# WIFI.net
KiCad netlist of a schematic drawn in Altium Designer
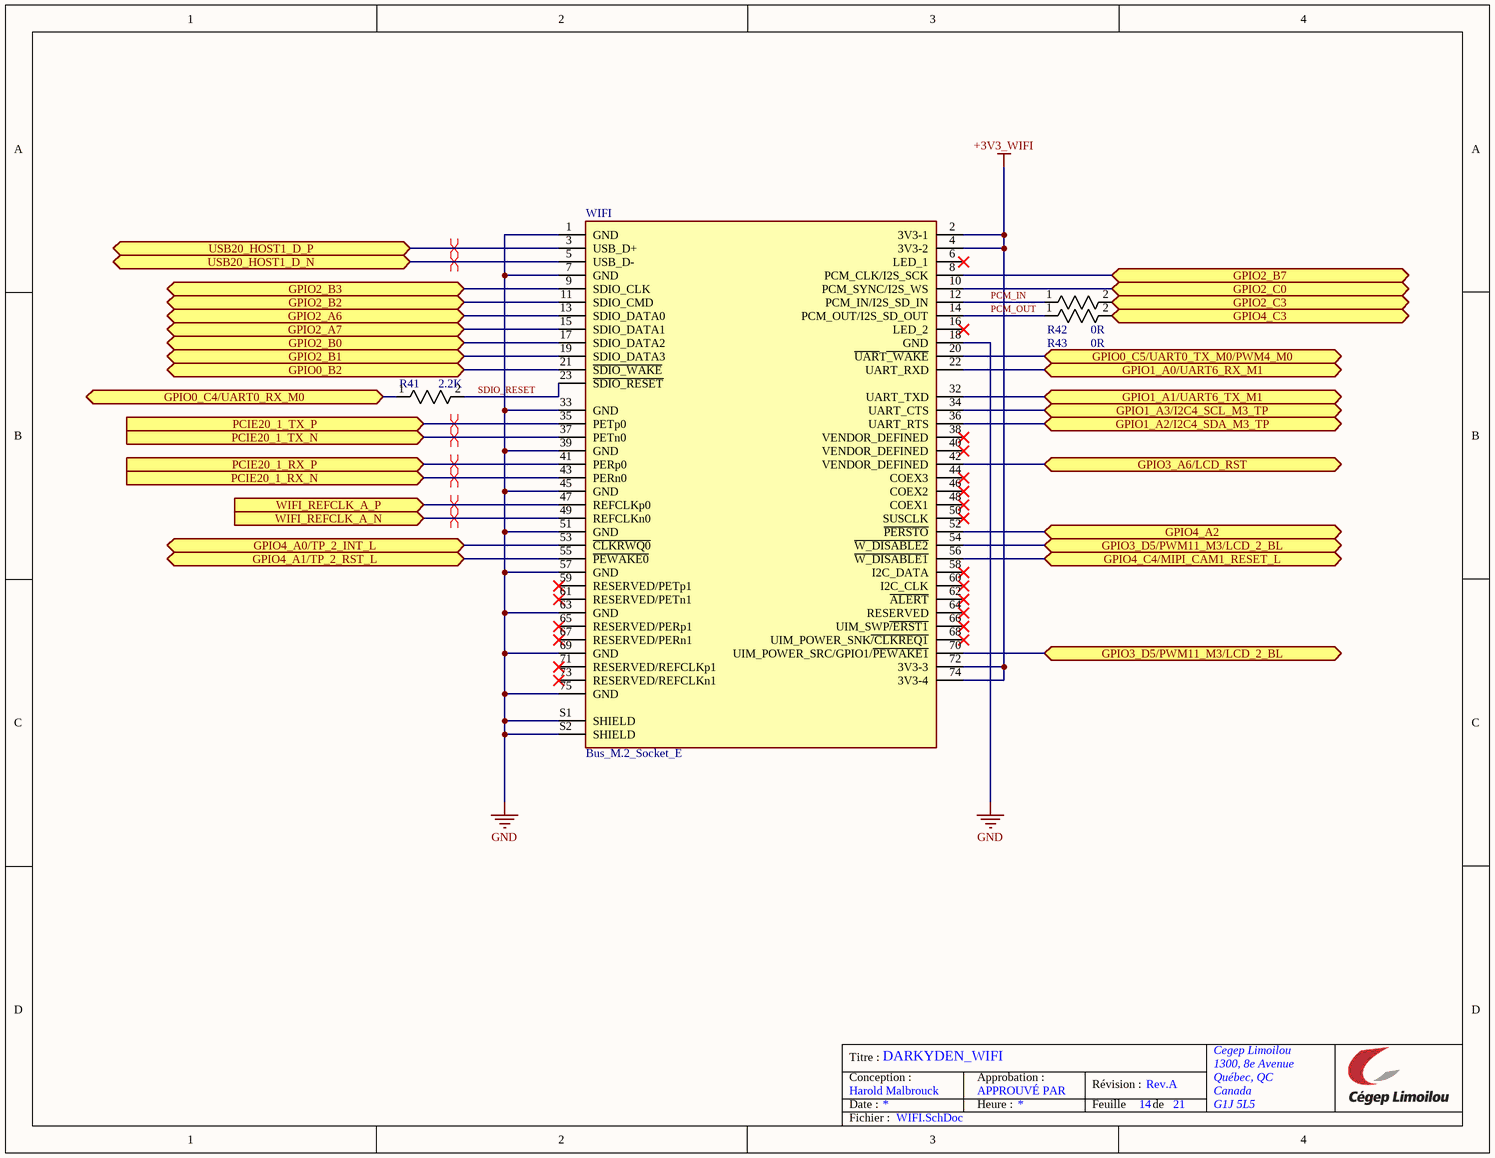
[diagram p0: WIFI.SchDoc]

(export (version "E")
  (design (tool "Eeschema 10.0.6"))
  (components
    (comp (ref "R41")
      (value "2.2K")
      (footprint "SamacSys:RESC1608X55N")
      (description "2.2 kOhm, ï¿½ 5%, 100 mW, 0603 [1608 Metric], Thick Film, General Purpose")
      (fields
        (field (name "MOUSER PART NUMBER") "667-ERJ-3GEYJ222V")
        (field (name "ARROW PART NUMBER") "ERJ-3GEYJ222V")
      )
      (libsource (lib "DARKYDEN") (part "ERJ-3GEYJ222V"))
    )
    (comp (ref "R42")
      (value "0R")
      (footprint "SamacSys:RESC1608X55N")
      (description "Zero Ohm Resistor, Jumper, 0603 [1608 Metric], Thick Film, 100 mW, 1 A, Surface Mount")
      (fields
        (field (name "MOUSER PART NUMBER") "667-ERJ-3GEY0R00V")
        (field (name "ARROW PART NUMBER") "ERJ-3GEY0R00V")
      )
      (libsource (lib "DARKYDEN") (part "ERJ-3GEY0R00V"))
    )
    (comp (ref "R43")
      (value "0R")
      (footprint "SamacSys:RESC1608X55N")
      (description "Zero Ohm Resistor, Jumper, 0603 [1608 Metric], Thick Film, 100 mW, 1 A, Surface Mount")
      (fields
        (field (name "MOUSER PART NUMBER") "667-ERJ-3GEY0R00V")
        (field (name "ARROW PART NUMBER") "ERJ-3GEY0R00V")
      )
      (libsource (lib "DARKYDEN") (part "ERJ-3GEY0R00V"))
    )
    (comp (ref "WIFI")
      (value "Bus_M.2_Socket_E")
      (footprint "AMPHENOL_MDT320E01001")
      (description "PCIe M.2 Connectors, Storage and Server Connector, P=0.5mm, H=3.2mm, Key E,30Î¼in Au Plating")
      (fields (field (name "MANUFACTURER PART NUMBER") "MDT320E01001") (field (name "MF") "Amphenol ICC"))
      (libsource (lib "Bus_M.2_Socket_E") (part "Bus_M.2_Socket_E"))
    )
  )
  (nets
    (net (code "1") (name "+3V3_WIFI") (class "Default")
      (node (ref "WIFI") (pin "2") (pinfunction "3V3-1_2") (pintype "power_in"))
      (node (ref "WIFI") (pin "4") (pinfunction "3V3-2_4") (pintype "power_in"))
      (node (ref "WIFI") (pin "72") (pinfunction "3V3-3_72") (pintype "power_in"))
      (node (ref "WIFI") (pin "74") (pinfunction "3V3-4_74") (pintype "power_in"))
    )
    (net (code "2") (name "/GPIO0_B2") (class "Default")
      (node (ref "WIFI") (pin "21") (pinfunction "~{SDIO_WAKE}_21") (pintype "passive"))
    )
    (net (code "3") (name "/GPIO0_C4{slash}UART0_RX_M0") (class "Default")
      (node (ref "R41") (pin "1") (pinfunction "1_1") (pintype "passive"))
    )
    (net (code "4") (name "/GPIO0_C5{slash}UART0_TX_M0{slash}PWM4_M0") (class "Default")
      (node (ref "WIFI") (pin "20") (pinfunction "~{UAR}T~{_WAKE}_20") (pintype "passive"))
    )
    (net (code "5") (name "/GPIO1_A0{slash}UART6_RX_M1") (class "Default")
      (node (ref "WIFI") (pin "22") (pinfunction "UART_RXD_22") (pintype "passive"))
    )
    (net (code "6") (name "/GPIO1_A1{slash}UART6_TX_M1") (class "Default")
      (node (ref "WIFI") (pin "32") (pinfunction "UART_TXD_32") (pintype "passive"))
    )
    (net (code "7") (name "/GPIO1_A2{slash}I2C4_SDA_M3_TP") (class "Default")
      (node (ref "WIFI") (pin "36") (pinfunction "UART_RTS_36") (pintype "passive"))
    )
    (net (code "8") (name "/GPIO1_A3{slash}I2C4_SCL_M3_TP") (class "Default")
      (node (ref "WIFI") (pin "34") (pinfunction "UART_CTS_34") (pintype "passive"))
    )
    (net (code "9") (name "/GPIO2_A6") (class "Default")
      (node (ref "WIFI") (pin "13") (pinfunction "SDIO_DATA0_13") (pintype "passive"))
    )
    (net (code "10") (name "/GPIO2_A7") (class "Default")
      (node (ref "WIFI") (pin "15") (pinfunction "SDIO_DATA1_15") (pintype "passive"))
    )
    (net (code "11") (name "/GPIO2_B0") (class "Default")
      (node (ref "WIFI") (pin "17") (pinfunction "SDIO_DATA2_17") (pintype "passive"))
    )
    (net (code "12") (name "/GPIO2_B1") (class "Default")
      (node (ref "WIFI") (pin "19") (pinfunction "SDIO_DATA3_19") (pintype "passive"))
    )
    (net (code "13") (name "/GPIO2_B2") (class "Default")
      (node (ref "WIFI") (pin "11") (pinfunction "SDIO_CMD_11") (pintype "passive"))
    )
    (net (code "14") (name "/GPIO2_B3") (class "Default")
      (node (ref "WIFI") (pin "9") (pinfunction "SDIO_CLK_9") (pintype "passive"))
    )
    (net (code "15") (name "/GPIO2_B7") (class "Default")
      (node (ref "WIFI") (pin "8") (pinfunction "PCM_CLK/I2S_SCK_8") (pintype "passive"))
    )
    (net (code "16") (name "/GPIO2_C0") (class "Default")
      (node (ref "WIFI") (pin "10") (pinfunction "PCM_SYNC/I2S_WS_10") (pintype "passive"))
    )
    (net (code "17") (name "/GPIO2_C3") (class "Default")
      (node (ref "R42") (pin "2") (pinfunction "2_2") (pintype "passive"))
    )
    (net (code "18") (name "/GPIO3_A6{slash}LCD_RST") (class "Default")
      (node (ref "WIFI") (pin "42") (pinfunction "VENDOR_DEFINED_42") (pintype "passive"))
    )
    (net (code "19") (name "/GPIO3_D5{slash}PWM11_M3{slash}LCD_2_BL") (class "Default")
      (node (ref "WIFI") (pin "54") (pinfunction "~{W_DISABLE2}_54") (pintype "passive"))
      (node (ref "WIFI") (pin "70") (pinfunction "UIM_POWER_SRC/GPIO1/~{PEWAKE1}_70") (pintype "passive"))
    )
    (net (code "20") (name "/GPIO4_A0{slash}TP_2_INT_L") (class "Default")
      (node (ref "WIFI") (pin "53") (pinfunction "~{CLKRWQ0}_53") (pintype "passive"))
    )
    (net (code "21") (name "/GPIO4_A1{slash}TP_2_RST_L") (class "Default")
      (node (ref "WIFI") (pin "55") (pinfunction "~{PEWAKE0}_55") (pintype "passive"))
    )
    (net (code "22") (name "/GPIO4_A2") (class "Default")
      (node (ref "WIFI") (pin "52") (pinfunction "~{PERSTO}_52") (pintype "passive"))
    )
    (net (code "23") (name "/GPIO4_C3") (class "Default")
      (node (ref "R43") (pin "2") (pinfunction "2_2") (pintype "passive"))
    )
    (net (code "24") (name "/GPIO4_C4{slash}MIPI_CAM1_RESET_L") (class "Default")
      (node (ref "WIFI") (pin "56") (pinfunction "~{W_DISABLE1}_56") (pintype "passive"))
    )
    (net (code "25") (name "/PCIE20_1_RX_N") (class "Default")
      (node (ref "WIFI") (pin "43") (pinfunction "PERn0_43") (pintype "passive"))
    )
    (net (code "26") (name "/PCIE20_1_RX_P") (class "Default")
      (node (ref "WIFI") (pin "41") (pinfunction "PERp0_41") (pintype "passive"))
    )
    (net (code "27") (name "/PCIE20_1_TX_N") (class "Default")
      (node (ref "WIFI") (pin "37") (pinfunction "PETn0_37") (pintype "passive"))
    )
    (net (code "28") (name "/PCIE20_1_TX_P") (class "Default")
      (node (ref "WIFI") (pin "35") (pinfunction "PETp0_35") (pintype "passive"))
    )
    (net (code "29") (name "/PCM_IN") (class "Default")
      (node (ref "R42") (pin "1") (pinfunction "1_1") (pintype "passive"))
      (node (ref "WIFI") (pin "12") (pinfunction "PCM_IN/I2S_SD_IN_12") (pintype "passive"))
    )
    (net (code "30") (name "/PCM_OUT") (class "Default")
      (node (ref "R43") (pin "1") (pinfunction "1_1") (pintype "passive"))
      (node (ref "WIFI") (pin "14") (pinfunction "PCM_OUT/I2S_SD_OUT_14") (pintype "passive"))
    )
    (net (code "31") (name "/SDIO_RESET") (class "Default")
      (node (ref "R41") (pin "2") (pinfunction "2_2") (pintype "passive"))
      (node (ref "WIFI") (pin "23") (pinfunction "~{SDIO_RESET}_23") (pintype "passive"))
    )
    (net (code "32") (name "/USB20_HOST1_D_N") (class "Default")
      (node (ref "WIFI") (pin "5") (pinfunction "USB_D-_5") (pintype "passive"))
    )
    (net (code "33") (name "/USB20_HOST1_D_P") (class "Default")
      (node (ref "WIFI") (pin "3") (pinfunction "USB_D+_3") (pintype "passive"))
    )
    (net (code "34") (name "/WIFI_REFCLK_A_N") (class "Default")
      (node (ref "WIFI") (pin "49") (pinfunction "REFCLKn0_49") (pintype "passive"))
    )
    (net (code "35") (name "/WIFI_REFCLK_A_P") (class "Default")
      (node (ref "WIFI") (pin "47") (pinfunction "REFCLKp0_47") (pintype "passive"))
    )
    (net (code "36") (name "GND") (class "Default")
      (node (ref "WIFI") (pin "1") (pinfunction "GND_1") (pintype "passive"))
      (node (ref "WIFI") (pin "18") (pinfunction "GND_18") (pintype "passive"))
      (node (ref "WIFI") (pin "33") (pinfunction "GND_33") (pintype "passive"))
      (node (ref "WIFI") (pin "39") (pinfunction "GND_39") (pintype "passive"))
      (node (ref "WIFI") (pin "45") (pinfunction "GND_45") (pintype "passive"))
      (node (ref "WIFI") (pin "51") (pinfunction "GND_51") (pintype "passive"))
      (node (ref "WIFI") (pin "57") (pinfunction "GND_57") (pintype "passive"))
      (node (ref "WIFI") (pin "63") (pinfunction "GND_63") (pintype "passive"))
      (node (ref "WIFI") (pin "69") (pinfunction "GND_69") (pintype "passive"))
      (node (ref "WIFI") (pin "7") (pinfunction "GND_7") (pintype "passive"))
      (node (ref "WIFI") (pin "75") (pinfunction "GND_75") (pintype "passive"))
      (node (ref "WIFI") (pin "S1") (pinfunction "SHIELD_S1") (pintype "passive"))
      (node (ref "WIFI") (pin "S2") (pinfunction "SHIELD_S2") (pintype "passive"))
    )
    (net (code "37") (name "unconnected-(WIFI-COEX1-Pad48)") (class "Default")
      (node (ref "WIFI") (pin "48") (pinfunction "COEX1_48") (pintype "passive+no_connect"))
    )
    (net (code "38") (name "unconnected-(WIFI-COEX2-Pad46)") (class "Default")
      (node (ref "WIFI") (pin "46") (pinfunction "COEX2_46") (pintype "passive+no_connect"))
    )
    (net (code "39") (name "unconnected-(WIFI-COEX3-Pad44)") (class "Default")
      (node (ref "WIFI") (pin "44") (pinfunction "COEX3_44") (pintype "passive+no_connect"))
    )
    (net (code "40") (name "unconnected-(WIFI-I2C_CLK-Pad60)") (class "Default")
      (node (ref "WIFI") (pin "60") (pinfunction "I2C_CLK_60") (pintype "passive+no_connect"))
    )
    (net (code "41") (name "unconnected-(WIFI-I2C_DATA-Pad58)") (class "Default")
      (node (ref "WIFI") (pin "58") (pinfunction "I2C_DATA_58") (pintype "passive+no_connect"))
    )
    (net (code "42") (name "unconnected-(WIFI-LED_1-Pad6)") (class "Default")
      (node (ref "WIFI") (pin "6") (pinfunction "LED_1_6") (pintype "passive+no_connect"))
    )
    (net (code "43") (name "unconnected-(WIFI-LED_2-Pad16)") (class "Default")
      (node (ref "WIFI") (pin "16") (pinfunction "LED_2_16") (pintype "passive+no_connect"))
    )
    (net (code "44") (name "unconnected-(WIFI-RESERVED-Pad64)") (class "Default")
      (node (ref "WIFI") (pin "64") (pinfunction "RESERVED_64") (pintype "passive+no_connect"))
    )
    (net (code "45") (name "unconnected-(WIFI-RESERVED{slash}PERn1-Pad67)") (class "Default")
      (node (ref "WIFI") (pin "67") (pinfunction "RESERVED/PERn1_67") (pintype "passive+no_connect"))
    )
    (net (code "46") (name "unconnected-(WIFI-RESERVED{slash}PERp1-Pad65)") (class "Default")
      (node (ref "WIFI") (pin "65") (pinfunction "RESERVED/PERp1_65") (pintype "passive+no_connect"))
    )
    (net (code "47") (name "unconnected-(WIFI-RESERVED{slash}PETn1-Pad61)") (class "Default")
      (node (ref "WIFI") (pin "61") (pinfunction "RESERVED/PETn1_61") (pintype "passive+no_connect"))
    )
    (net (code "48") (name "unconnected-(WIFI-RESERVED{slash}PETp1-Pad59)") (class "Default")
      (node (ref "WIFI") (pin "59") (pinfunction "RESERVED/PETp1_59") (pintype "passive+no_connect"))
    )
    (net (code "49") (name "unconnected-(WIFI-RESERVED{slash}REFCLKn1-Pad73)") (class "Default")
      (node (ref "WIFI") (pin "73") (pinfunction "RESERVED/REFCLKn1_73") (pintype "passive+no_connect"))
    )
    (net (code "50") (name "unconnected-(WIFI-RESERVED{slash}REFCLKp1-Pad71)") (class "Default")
      (node (ref "WIFI") (pin "71") (pinfunction "RESERVED/REFCLKp1_71") (pintype "passive+no_connect"))
    )
    (net (code "51") (name "unconnected-(WIFI-SUSCLK-Pad50)") (class "Default")
      (node (ref "WIFI") (pin "50") (pinfunction "SUSCLK_50") (pintype "passive+no_connect"))
    )
    (net (code "52") (name "unconnected-(WIFI-UIM_POWER_SNK~{{slash}CLKREQ1}-Pad68)") (class "Default")
      (node (ref "WIFI") (pin "68") (pinfunction "UIM_POWER_SNK~{/CLKREQ1}_68") (pintype "passive+no_connect"))
    )
    (net (code "53") (name "unconnected-(WIFI-UIM_SWP~{{slash}ERST1}-Pad66)") (class "Default")
      (node (ref "WIFI") (pin "66") (pinfunction "UIM_SWP~{/ERST1}_66") (pintype "passive+no_connect"))
    )
    (net (code "54") (name "unconnected-(WIFI-VENDOR_DEFINED-Pad38)") (class "Default")
      (node (ref "WIFI") (pin "38") (pinfunction "VENDOR_DEFINED_38") (pintype "passive+no_connect"))
    )
    (net (code "55") (name "unconnected-(WIFI-VENDOR_DEFINED-Pad40)") (class "Default")
      (node (ref "WIFI") (pin "40") (pinfunction "VENDOR_DEFINED_40") (pintype "passive+no_connect"))
    )
    (net (code "56") (name "unconnected-(WIFI-~{ALERT}-Pad62)") (class "Default")
      (node (ref "WIFI") (pin "62") (pinfunction "~{ALERT}_62") (pintype "passive+no_connect"))
    )
  )
)
